# 18V_ESB.net
KiCad netlist of a schematic drawn in Altium Designer
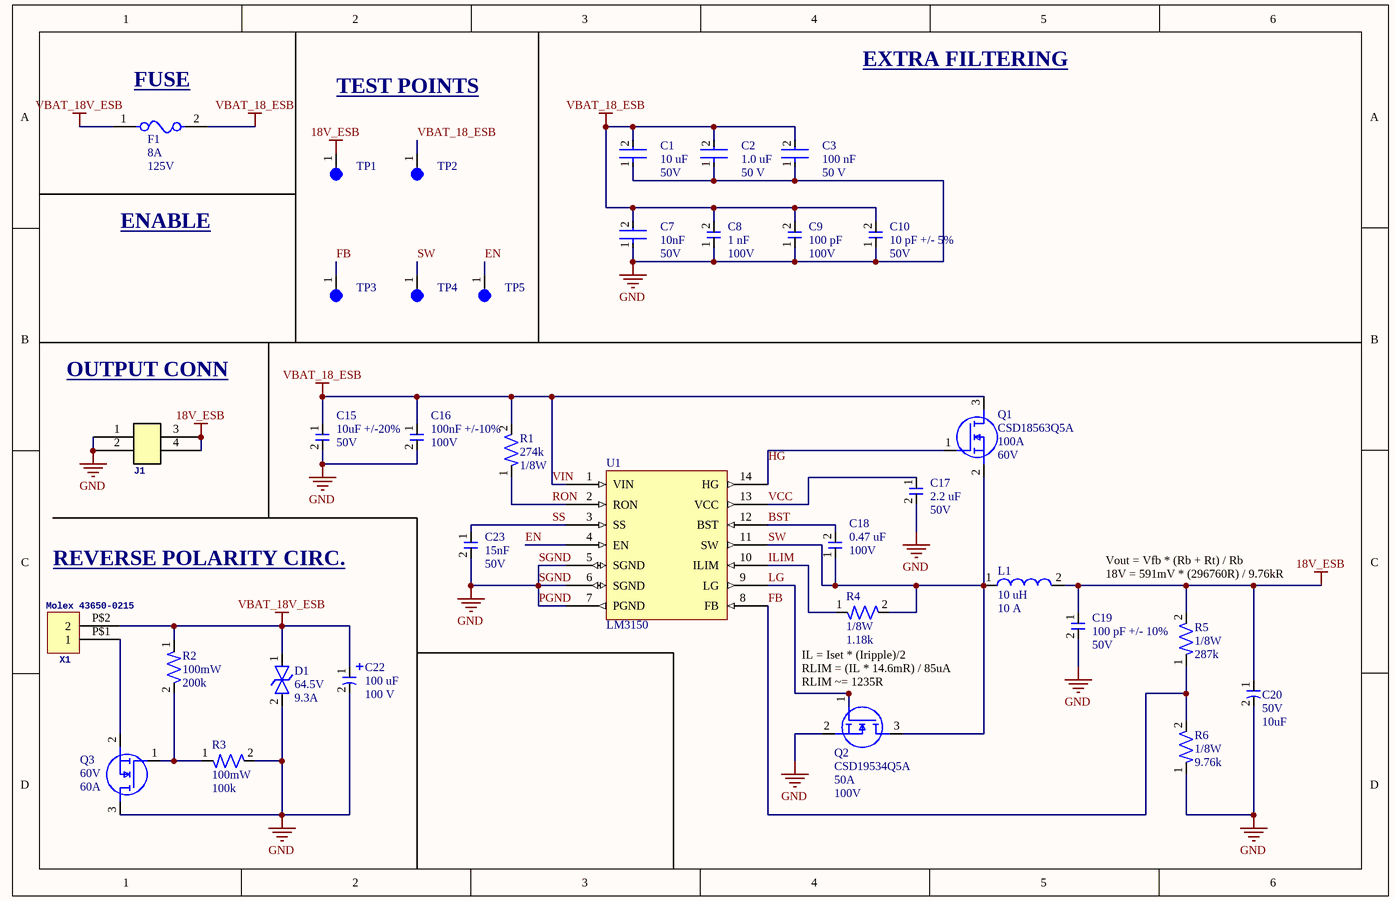
[diagram p0: 18V_ESB.SchDoc]

(export (version "E")
  (design (tool "Eeschema 10.0.6"))
  (components
    (comp (ref "C1")
      (value "CL32B106KBJNNNE")
      (footprint "MasterLib:CAP-1210")
      (description "CAP CER 10UF 50V X7R 1210")
      (fields (field (name "VOLTAGE") "50V") (field (name "CAPACITANCE") "10 uF"))
      (libsource (lib "JLC_25") (part "CAP-10U-0002"))
    )
    (comp (ref "C2")
      (value "CC0805KKX7R9BB105")
      (footprint "MasterLib:CAP-0805")
      (description "CAP CER 1UF 50V X7R 0805")
      (fields (field (name "VOLTAGE") "50 V") (field (name "CAPACITANCE") "1.0 uF"))
      (libsource (lib "JLC_25") (part "CAP-1U-0001"))
    )
    (comp (ref "C3")
      (value "CC0805KRX7R9BB104")
      (footprint "MasterLib:CAP-0805")
      (description "CAP CER 0.1UF 50V X7R 0805")
      (fields (field (name "VOLTAGE RATING") "50 V") (field (name "CAPACITANCE") "100 nF"))
      (libsource (lib "JLC_25") (part "CAP-0.1U-0002"))
    )
    (comp (ref "C7")
      (value "GRM2195C1H103JA01D")
      (footprint "MasterLib:CAP-0805")
      (description "CAP CER 10000PF 50V C0G/NP0 0805")
      (fields (field (name "VOLTAGE") "50V") (field (name "CAPACITANCE") "10nF"))
      (libsource (lib "JLC_25") (part "CAP-10N-0001"))
    )
    (comp (ref "C8")
      (value "CDR01BX102BKUS7185")
      (footprint "CAP-0805")
      (description "1000 pF ±10% 100V Ceramic Capacitor BX 0805 (2012 Metric)")
      (fields (field (name "CAPACITANCE") "1 nF") (field (name "VOLTAGE RATING") "100V"))
      (libsource (lib "MasterLib") (part "CAP-1N-0003"))
    )
    (comp (ref "C9")
      (value "0603N101J101CT")
      (footprint "CAP-0603")
      (description "100 pF ±5% 100V Ceramic Capacitor C0G, NP0 0603 (1608 Metric)")
      (fields
        (field (name "TOLERANCE") "+/-5%")
        (field (name "CAPACITANCE") "100 pF")
        (field (name "VOLTAGE") "100V")
      )
      (libsource (lib "MasterLib") (part "CAP-100P-0002"))
    )
    (comp (ref "C10")
      (value "0603N100J500CT")
      (footprint "CAP-0603")
      (description "10 pF ±5% 50V Ceramic Capacitor C0G, NP0 0603 (1608 Metric)")
      (fields
        (field (name "MANUFACTURER") "Walshin Technology Corporation")
        (field (name "CAPACITANCE") "10 pF +/- 5%")
        (field (name "VOLTAGE RATING") "50V")
      )
      (libsource (lib "MasterLib") (part "CAP-10P-0001"))
    )
    (comp (ref "C15")
      (value "CL31B106KBHNNNE")
      (footprint "CAP-1206")
      (description "10 µF ±10% 50V Ceramic Capacitor X7R 1206 (3216 Metric)")
      (fields
        (field (name "MANUFACTURER") "Samsung Electro-Mechanics")
        (field (name "CAPACITANCE") "10uF +/-20%")
        (field (name "VOLTAGE RATING") "50V")
      )
      (libsource (lib "MasterLib") (part "CAP-10U-0001"))
    )
    (comp (ref "C16")
      (value "CC0603KRX7R0BB104")
      (footprint "CAP-0603")
      (description "CAP CER 0.1UF 100V X7R 0603")
      (fields
        (field (name "MANUFACTURER") "YAGEO")
        (field (name "CAPACITANCE") "100nF +/-10%")
        (field (name "VOLTAGE RATING") "100V")
      )
      (libsource (lib "MasterLib") (part "CAP-100N-0001"))
    )
    (comp (ref "C17")
      (value "UMK107BBJ225KA-T")
      (footprint "CAP-0603")
      (description "2.2 µF ±10% 50V Ceramic Capacitor X5R 0603 (1608 Metric)")
      (fields (field (name "CAPACITANCE") "2.2 uF") (field (name "OLTAGE") "50V"))
      (libsource (lib "MasterLib") (part "CAP-2.2U-0001"))
    )
    (comp (ref "C18")
      (value "KAM21KR72A474KL")
      (footprint "CAP-0805")
      (description "0.47 µF ±10% 100V Ceramic Capacitor X7R 0805 (2012 Metric)")
      (fields
        (field (name "TOLERANCE") "+/- 10%")
        (field (name "CAPACITANCE") "0.47 uF")
        (field (name "VOLTAGE") "100V")
      )
      (libsource (lib "MasterLib") (part "CAP-0.47U-0001"))
    )
    (comp (ref "C19")
      (value "0402B101K500NT")
      (footprint "CAP-0402")
      (description "50V 100pF X7R ±10% 0402 Multilayer Ceramic Capacitors MLCC - SMD/SMT ROHS")
      (fields
        (field (name "JLC PART NUMBER") "C2991538")
        (field (name "CAPACITANCE") "100 pF +/- 10%")
        (field (name "VOLTAGE") "50V")
      )
      (libsource (lib "MasterLib") (part "CAP-100P-0001-JLC"))
    )
    (comp (ref "C20")
      (value "EEE-FK1H100UR")
      (footprint "ELEC-10uF")
      (description "10 µF 50 V Aluminum Electrolytic Capacitors Radial, Can - SMD 2000 Hrs @ 105°C")
      (fields
        (field (name "MANUFACTURER PART NUMBER") "RC0402FR-074K7P")
        (field (name "MANUFACTURER") "YAGEO")
        (field (name "VOLTAGE") "50V")
        (field (name "CAPACITANCE") "10uF")
      )
      (libsource (lib "MasterLib") (part "ELEC-10U-0001"))
    )
    (comp (ref "C22")
      (value "100SEV100M12.5X16")
      (footprint "ELEC-100U-0001")
      (description "100 µF 100 V Aluminum Electrolytic Capacitors Radial, Can - SMD 2000 Hrs @ 85°C")
      (fields
        (field (name "MANUFACTURER") "Rubycon")
        (field (name "TOLERANCE") "+/- 20%")
        (field (name "CAPACITANCE") "100 uF")
        (field (name "VOLTAGE") "100 V")
      )
      (libsource (lib "MasterLib") (part "ELEC-100U-0001"))
    )
    (comp (ref "C23")
      (value "CC0402JRX7R9BB153")
      (footprint "CAP-0402")
      (description "CAP CER 0.015UF 50V X7R 0402")
      (fields (field (name "PARAMETER 1") "15nF") (field (name "PARAMETER 2") "50V"))
      (libsource (lib "MasterLib") (part "CAP-15N-0001"))
    )
    (comp (ref "D1")
      (value "SMBJ40CA")
      (footprint "JLC_25:DO-214AA (SMBJ)")
      (description "TVS DIODE 40VWM 64.5VC DO214AA")
      (fields (field (name "VOLTAGE RATING") "64.5V") (field (name "CURRENT RATING") "9.3A"))
      (libsource (lib "JLC_25") (part "DIO-TVS-0001"))
    )
    (comp (ref "F1")
      (value "01550900M")
      (footprint "JLC_25:FUSE-0001")
      (description "FUSE BLOK CARTRIDGE 125V 10A SMD")
      (fields (field (name "FUSE CURRENT") "8A") (field (name "VOLTAGE RATING") "125V"))
      (libsource (lib "JLC_25") (part "FUSE-0001"))
    )
    (comp (ref "J1")
      (value "Molex 43045-0412")
      (footprint "JLC_25:CONN-4POS-0002")
      (description "CONN HEADER VERT 4POS 3MM")
      (libsource (lib "JLC_25") (part "CONN-4POS-0002"))
    )
    (comp (ref "L1")
      (value "SRP1270-100M")
      (footprint "PWRIND-10U-0002")
      (description "10 µH Shielded Drum Core, Wirewound Inductor 10 A 16.8mOhm Max Nonstandard")
      (fields
        (field (name "TOLERANCE") "+/- 20%")
        (field (name "INDUCTANCE") "10 uH")
        (field (name "DCI") "10 A")
      )
      (libsource (lib "MasterLib") (part "PWRIND-10U-0002"))
    )
    (comp (ref "Q1")
      (value "CSD18563Q5A")
      (footprint "8-VSONP")
      (description "MOSFET N-CH 60V 100A 8VSON")
      (fields
        (field (name "MANUFACTURER PART NUMBER") "T2N7002AK,LM")
        (field (name "MANUFACTURER") "Toshiba")
        (field (name "ID-CONTINUOUS") "100A")
        (field (name "VDS-MAX") "60V")
      )
      (libsource (lib "MasterLib") (part "NMOS-100A-0001"))
    )
    (comp (ref "Q2")
      (value "CSD19534Q5A")
      (footprint "8-VSONP")
      (description "MOSFET N-CH 100V 50A 8VSON")
      (fields
        (field (name "MANUFACTURER PART NUMBER") "T2N7002AK,LM")
        (field (name "MANUFACTURER") "Toshiba")
        (field (name "ID-CONTINUOUS") "50A")
        (field (name "VDS-MAX") "100V")
      )
      (libsource (lib "MasterLib") (part "NMOS-50A-0001"))
    )
    (comp (ref "Q3")
      (value "CSD18543Q3AT")
      (footprint "JLC_25:IC-8VSONCLIP")
      (description "MOSFET N-CH 60V 12A/60A 8VSON")
      (fields (field (name "VOLTAGE") "60V") (field (name "CONTINUOUS CURRENT") "60A"))
      (libsource (lib "JLC_25") (part "NMOS-60A-0001"))
    )
    (comp (ref "R1")
      (value "RC0805FR-07274KL")
      (footprint "RES-0805")
      (description "274 kOhms ±1% 0.125W, 1/8W Chip Resistor 0805 (2012 Metric) Moisture Resistant Thick Film")
      (fields (field (name "RESISTANCE") "274k") (field (name "POWER") "1/8W"))
      (libsource (lib "MasterLib") (part "RES-274k-0001"))
    )
    (comp (ref "R2")
      (value "RC0603FR-07200KL")
      (footprint "MasterLib:RES-0603")
      (description "RES SMD 200K OHM 1% 1/10W 0603")
      (fields
        (field (name "TOLERANCE") "1%")
        (field (name "POWER") "100mW")
        (field (name "RESISTANCE") "200k")
      )
      (libsource (lib "JLC_25") (part "RES-200k-0001"))
    )
    (comp (ref "R3")
      (value "RC0603FR-07100KL")
      (footprint "MasterLib:RES-0603")
      (description "RES SMD 100K OHM 1% 1/10W 0603")
      (fields
        (field (name "TOLERANCE") "1%")
        (field (name "POWER") "100mW")
        (field (name "RESISTANCE") "100k")
      )
      (libsource (lib "JLC_25") (part "RES-100k-0001"))
    )
    (comp (ref "R4")
      (value "RC0805FR-071K18L")
      (footprint "RES-0805")
      (description "1.18 kOhms ±1% 0.125W, 1/8W Chip Resistor 0805 (2012 Metric) Moisture Resistant Thick Film")
      (fields (field (name "POWER") "1/8W") (field (name "RESISTANCE") "1.18k"))
      (libsource (lib "MasterLib") (part "RES-1.18k-0001"))
    )
    (comp (ref "R5")
      (value "RC0805FR-07287KL")
      (footprint "RES-0805")
      (description "287 kOhms ±1% 0.125W, 1/8W Chip Resistor 0805 (2012 Metric) Moisture Resistant Thick Film")
      (fields (field (name "POWER") "1/8W") (field (name "RESISTANCE") "287k"))
      (libsource (lib "MasterLib") (part "RES-287k-0001"))
    )
    (comp (ref "R6")
      (value "RC0805FR-079K76L")
      (footprint "RES-0805")
      (description "9.76 kOhms ±1% 0.125W, 1/8W Chip Resistor 0805 (2012 Metric) Moisture Resistant Thick Film")
      (fields (field (name "POWER") "1/8W") (field (name "RESISTANCE") "9.76k"))
      (libsource (lib "MasterLib") (part "RES-9.76k-0001"))
    )
    (comp (ref "TP1")
      (value "5003")
      (footprint "TEST-POINT-0001")
      (description "Oranange PC Test Point, Miniature Phoisphor Bronze Silver Plating Through Hole Mounting Type")
      (libsource (lib "*") (part "TEST-POINT-0001"))
    )
    (comp (ref "TP2")
      (value "5003")
      (footprint "TEST-POINT-0001")
      (description "Oranange PC Test Point, Miniature Phoisphor Bronze Silver Plating Through Hole Mounting Type")
      (libsource (lib "*") (part "TEST-POINT-0001"))
    )
    (comp (ref "TP3")
      (value "5003")
      (footprint "TEST-POINT-0001")
      (description "Oranange PC Test Point, Miniature Phoisphor Bronze Silver Plating Through Hole Mounting Type")
      (libsource (lib "*") (part "TEST-POINT-0001"))
    )
    (comp (ref "TP4")
      (value "5003")
      (footprint "TEST-POINT-0001")
      (description "Oranange PC Test Point, Miniature Phoisphor Bronze Silver Plating Through Hole Mounting Type")
      (libsource (lib "*") (part "TEST-POINT-0001"))
    )
    (comp (ref "TP5")
      (value "5003")
      (footprint "TEST-POINT-0001")
      (description "Oranange PC Test Point, Miniature Phoisphor Bronze Silver Plating Through Hole Mounting Type")
      (libsource (lib "*") (part "TEST-POINT-0001"))
    )
    (comp (ref "U1")
      (value "LM3150")
      (footprint "IC-14HTSSOP")
      (description "Buck Regulator Positive Output Step-Down DC-DC Controller IC 14-HTSSOP")
      (libsource (lib "MasterLib") (part "IC-ESB-0001"))
    )
    (comp (ref "X1")
      (value "Molex 43650-0215")
      (footprint "43650-0215")
      (libsource (lib "Molex Microfit") (part "Micro-Fit Molex 2 Pin Vertical"))
    )
  )
  (nets
    (net (code "1") (name "/BST") (class "Default")
      (node (ref "C18") (pin "2") (pinfunction "2_2") (pintype "passive"))
      (node (ref "U1") (pin "12") (pinfunction "BST_12") (pintype "input"))
    )
    (net (code "2") (name "/EN") (class "Default")
      (node (ref "TP5") (pin "1") (pinfunction "0_1") (pintype "passive"))
      (node (ref "U1") (pin "4") (pinfunction "EN_4") (pintype "input"))
    )
    (net (code "3") (name "/FB") (class "Default")
      (node (ref "R5") (pin "1") (pinfunction "1_1") (pintype "passive"))
      (node (ref "R6") (pin "2") (pinfunction "2_2") (pintype "passive"))
      (node (ref "TP3") (pin "1") (pinfunction "0_1") (pintype "passive"))
      (node (ref "U1") (pin "8") (pinfunction "FB_8") (pintype "input"))
    )
    (net (code "4") (name "/HG") (class "Default")
      (node (ref "Q1") (pin "1") (pinfunction "G_1") (pintype "passive"))
      (node (ref "U1") (pin "14") (pinfunction "HG_14") (pintype "output"))
    )
    (net (code "5") (name "/ILIM") (class "Default")
      (node (ref "R4") (pin "1") (pinfunction "1_1") (pintype "passive"))
      (node (ref "U1") (pin "10") (pinfunction "ILIM_10") (pintype "input"))
    )
    (net (code "6") (name "/LG") (class "Default")
      (node (ref "Q2") (pin "1") (pinfunction "G_1") (pintype "passive"))
      (node (ref "U1") (pin "9") (pinfunction "LG_9") (pintype "output"))
    )
    (net (code "7") (name "/RON") (class "Default")
      (node (ref "R1") (pin "1") (pinfunction "1_1") (pintype "passive"))
      (node (ref "U1") (pin "2") (pinfunction "RON_2") (pintype "input"))
    )
    (net (code "8") (name "/SS") (class "Default")
      (node (ref "C23") (pin "1") (pinfunction "1_1") (pintype "passive"))
      (node (ref "U1") (pin "3") (pinfunction "SS_3") (pintype "input"))
    )
    (net (code "9") (name "/SW") (class "Default")
      (node (ref "C18") (pin "1") (pinfunction "1_1") (pintype "passive"))
      (node (ref "L1") (pin "1") (pinfunction "1_1") (pintype "passive"))
      (node (ref "Q1") (pin "2") (pinfunction "S_2") (pintype "passive"))
      (node (ref "Q2") (pin "3") (pinfunction "D_3") (pintype "passive"))
      (node (ref "R4") (pin "2") (pinfunction "2_2") (pintype "passive"))
      (node (ref "TP4") (pin "1") (pinfunction "0_1") (pintype "passive"))
      (node (ref "U1") (pin "11") (pinfunction "SW_11") (pintype "output"))
    )
    (net (code "10") (name "/VCC") (class "Default")
      (node (ref "C17") (pin "1") (pinfunction "1_1") (pintype "passive"))
      (node (ref "U1") (pin "13") (pinfunction "VCC_13") (pintype "output"))
    )
    (net (code "11") (name "18V_ESB") (class "Default")
      (node (ref "C19") (pin "1") (pinfunction "1_1") (pintype "passive"))
      (node (ref "C20") (pin "1") (pinfunction "1_1") (pintype "passive"))
      (node (ref "J1") (pin "3") (pinfunction "3_3") (pintype "passive"))
      (node (ref "J1") (pin "4") (pinfunction "4_4") (pintype "passive"))
      (node (ref "L1") (pin "2") (pinfunction "2_2") (pintype "passive"))
      (node (ref "R5") (pin "2") (pinfunction "2_2") (pintype "passive"))
      (node (ref "TP1") (pin "1") (pinfunction "0_1") (pintype "passive"))
    )
    (net (code "12") (name "GND") (class "Default")
      (node (ref "C1") (pin "1") (pinfunction "1_1") (pintype "passive"))
      (node (ref "C10") (pin "1") (pinfunction "1_1") (pintype "passive"))
      (node (ref "C15") (pin "2") (pinfunction "2_2") (pintype "passive"))
      (node (ref "C16") (pin "2") (pinfunction "2_2") (pintype "passive"))
      (node (ref "C17") (pin "2") (pinfunction "2_2") (pintype "passive"))
      (node (ref "C19") (pin "2") (pinfunction "2_2") (pintype "passive"))
      (node (ref "C2") (pin "1") (pinfunction "1_1") (pintype "passive"))
      (node (ref "C20") (pin "2") (pinfunction "2_2") (pintype "passive"))
      (node (ref "C22") (pin "2") (pinfunction "2_2") (pintype "passive"))
      (node (ref "C23") (pin "2") (pinfunction "2_2") (pintype "passive"))
      (node (ref "C3") (pin "1") (pinfunction "1_1") (pintype "passive"))
      (node (ref "C7") (pin "1") (pinfunction "1_1") (pintype "passive"))
      (node (ref "C8") (pin "1") (pinfunction "1_1") (pintype "passive"))
      (node (ref "C9") (pin "1") (pinfunction "1_1") (pintype "passive"))
      (node (ref "D1") (pin "2") (pintype "passive"))
      (node (ref "J1") (pin "1") (pinfunction "1_1") (pintype "passive"))
      (node (ref "J1") (pin "2") (pinfunction "2_2") (pintype "passive"))
      (node (ref "Q2") (pin "2") (pinfunction "S_2") (pintype "passive"))
      (node (ref "Q3") (pin "3") (pinfunction "D_3") (pintype "passive"))
      (node (ref "R3") (pin "2") (pinfunction "2_2") (pintype "passive"))
      (node (ref "R6") (pin "1") (pinfunction "1_1") (pintype "passive"))
      (node (ref "U1") (pin "5") (pinfunction "SGND_5") (pintype "bidirectional"))
      (node (ref "U1") (pin "6") (pinfunction "SGND_6") (pintype "bidirectional"))
      (node (ref "U1") (pin "7") (pinfunction "PGND_7") (pintype "output"))
    )
    (net (code "13") (name "Net-(Q3-G)") (class "Default")
      (node (ref "Q3") (pin "1") (pinfunction "G_1") (pintype "passive"))
      (node (ref "R2") (pin "2") (pinfunction "2_2") (pintype "passive"))
      (node (ref "R3") (pin "1") (pinfunction "1_1") (pintype "passive"))
    )
    (net (code "14") (name "Net-(Q3-S)") (class "Default")
      (node (ref "Q3") (pin "2") (pinfunction "S_2") (pintype "passive"))
      (node (ref "X1") (pin "P$1") (pinfunction "1_P$1") (pintype "passive"))
    )
    (net (code "15") (name "VBAT_18V_ESB") (class "Default")
      (node (ref "C22") (pin "1") (pinfunction "1_1") (pintype "passive"))
      (node (ref "D1") (pin "1") (pintype "passive"))
      (node (ref "F1") (pin "1") (pinfunction "1_1") (pintype "passive"))
      (node (ref "R2") (pin "1") (pinfunction "1_1") (pintype "passive"))
      (node (ref "X1") (pin "P$2") (pinfunction "2_P$2") (pintype "passive"))
    )
    (net (code "16") (name "VBAT_18_ESB") (class "Default")
      (node (ref "C1") (pin "2") (pinfunction "2_2") (pintype "passive"))
      (node (ref "C10") (pin "2") (pinfunction "2_2") (pintype "passive"))
      (node (ref "C15") (pin "1") (pinfunction "1_1") (pintype "passive"))
      (node (ref "C16") (pin "1") (pinfunction "1_1") (pintype "passive"))
      (node (ref "C2") (pin "2") (pinfunction "2_2") (pintype "passive"))
      (node (ref "C3") (pin "2") (pinfunction "2_2") (pintype "passive"))
      (node (ref "C7") (pin "2") (pinfunction "2_2") (pintype "passive"))
      (node (ref "C8") (pin "2") (pinfunction "2_2") (pintype "passive"))
      (node (ref "C9") (pin "2") (pinfunction "2_2") (pintype "passive"))
      (node (ref "F1") (pin "2") (pinfunction "2_2") (pintype "passive"))
      (node (ref "Q1") (pin "3") (pinfunction "D_3") (pintype "passive"))
      (node (ref "R1") (pin "2") (pinfunction "2_2") (pintype "passive"))
      (node (ref "TP2") (pin "1") (pinfunction "0_1") (pintype "passive"))
      (node (ref "U1") (pin "1") (pinfunction "VIN_1") (pintype "input"))
    )
  )
)
